# Power.net
KiCad netlist of a schematic drawn in Altium Designer
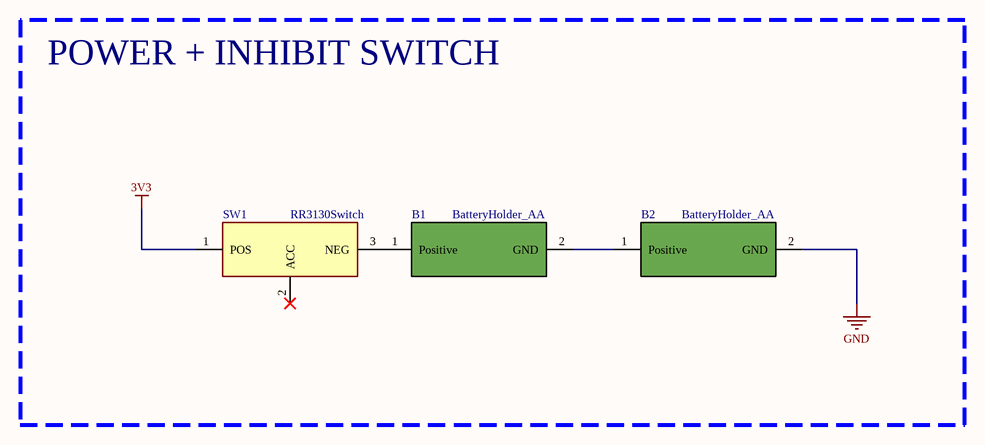
[diagram p0: Power.SchDoc]

(export (version "E")
  (design (tool "Eeschema 10.0.6"))
  (components
    (comp (ref "B1")
      (value "BatteryHolder_AA")
      (footprint "BatteryHolder_AA")
      (description "Keystone Electronics 1088")
      (libsource (lib "RocketLib") (part "BatteryHolder_AA"))
    )
    (comp (ref "B2")
      (value "BatteryHolder_AA")
      (footprint "BatteryHolder_AA")
      (description "Keystone Electronics 1088")
      (libsource (lib "RocketLib") (part "BatteryHolder_AA"))
    )
    (comp (ref "SW1")
      (value "RR3130Switch")
      (footprint "RR3130Switch")
      (description "SWITCH ROCKER SPST 10A 125V")
      (libsource (lib "RocketLib") (part "RR3130Switch"))
    )
  )
  (nets
    (net (code "1") (name "3V3") (class "Default")
      (node (ref "SW1") (pin "1") (pinfunction "POS_1") (pintype "passive"))
    )
    (net (code "2") (name "GND") (class "Default")
      (node (ref "B2") (pin "2") (pinfunction "GND_2") (pintype "passive"))
    )
    (net (code "3") (name "Net-(B1-GND)") (class "Default")
      (node (ref "B1") (pin "2") (pinfunction "GND_2") (pintype "passive"))
      (node (ref "B2") (pin "1") (pinfunction "Positive_1") (pintype "passive"))
    )
    (net (code "4") (name "Net-(B1-Positive)") (class "Default")
      (node (ref "B1") (pin "1") (pinfunction "Positive_1") (pintype "passive"))
      (node (ref "SW1") (pin "3") (pinfunction "NEG_3") (pintype "passive"))
    )
    (net (code "5") (name "unconnected-(SW1-ACC-Pad2)") (class "Default")
      (node (ref "SW1") (pin "2") (pinfunction "ACC_2") (pintype "passive+no_connect"))
    )
  )
)
